# ValetudoV2.net
KiCad netlist of a schematic drawn in EAGLE
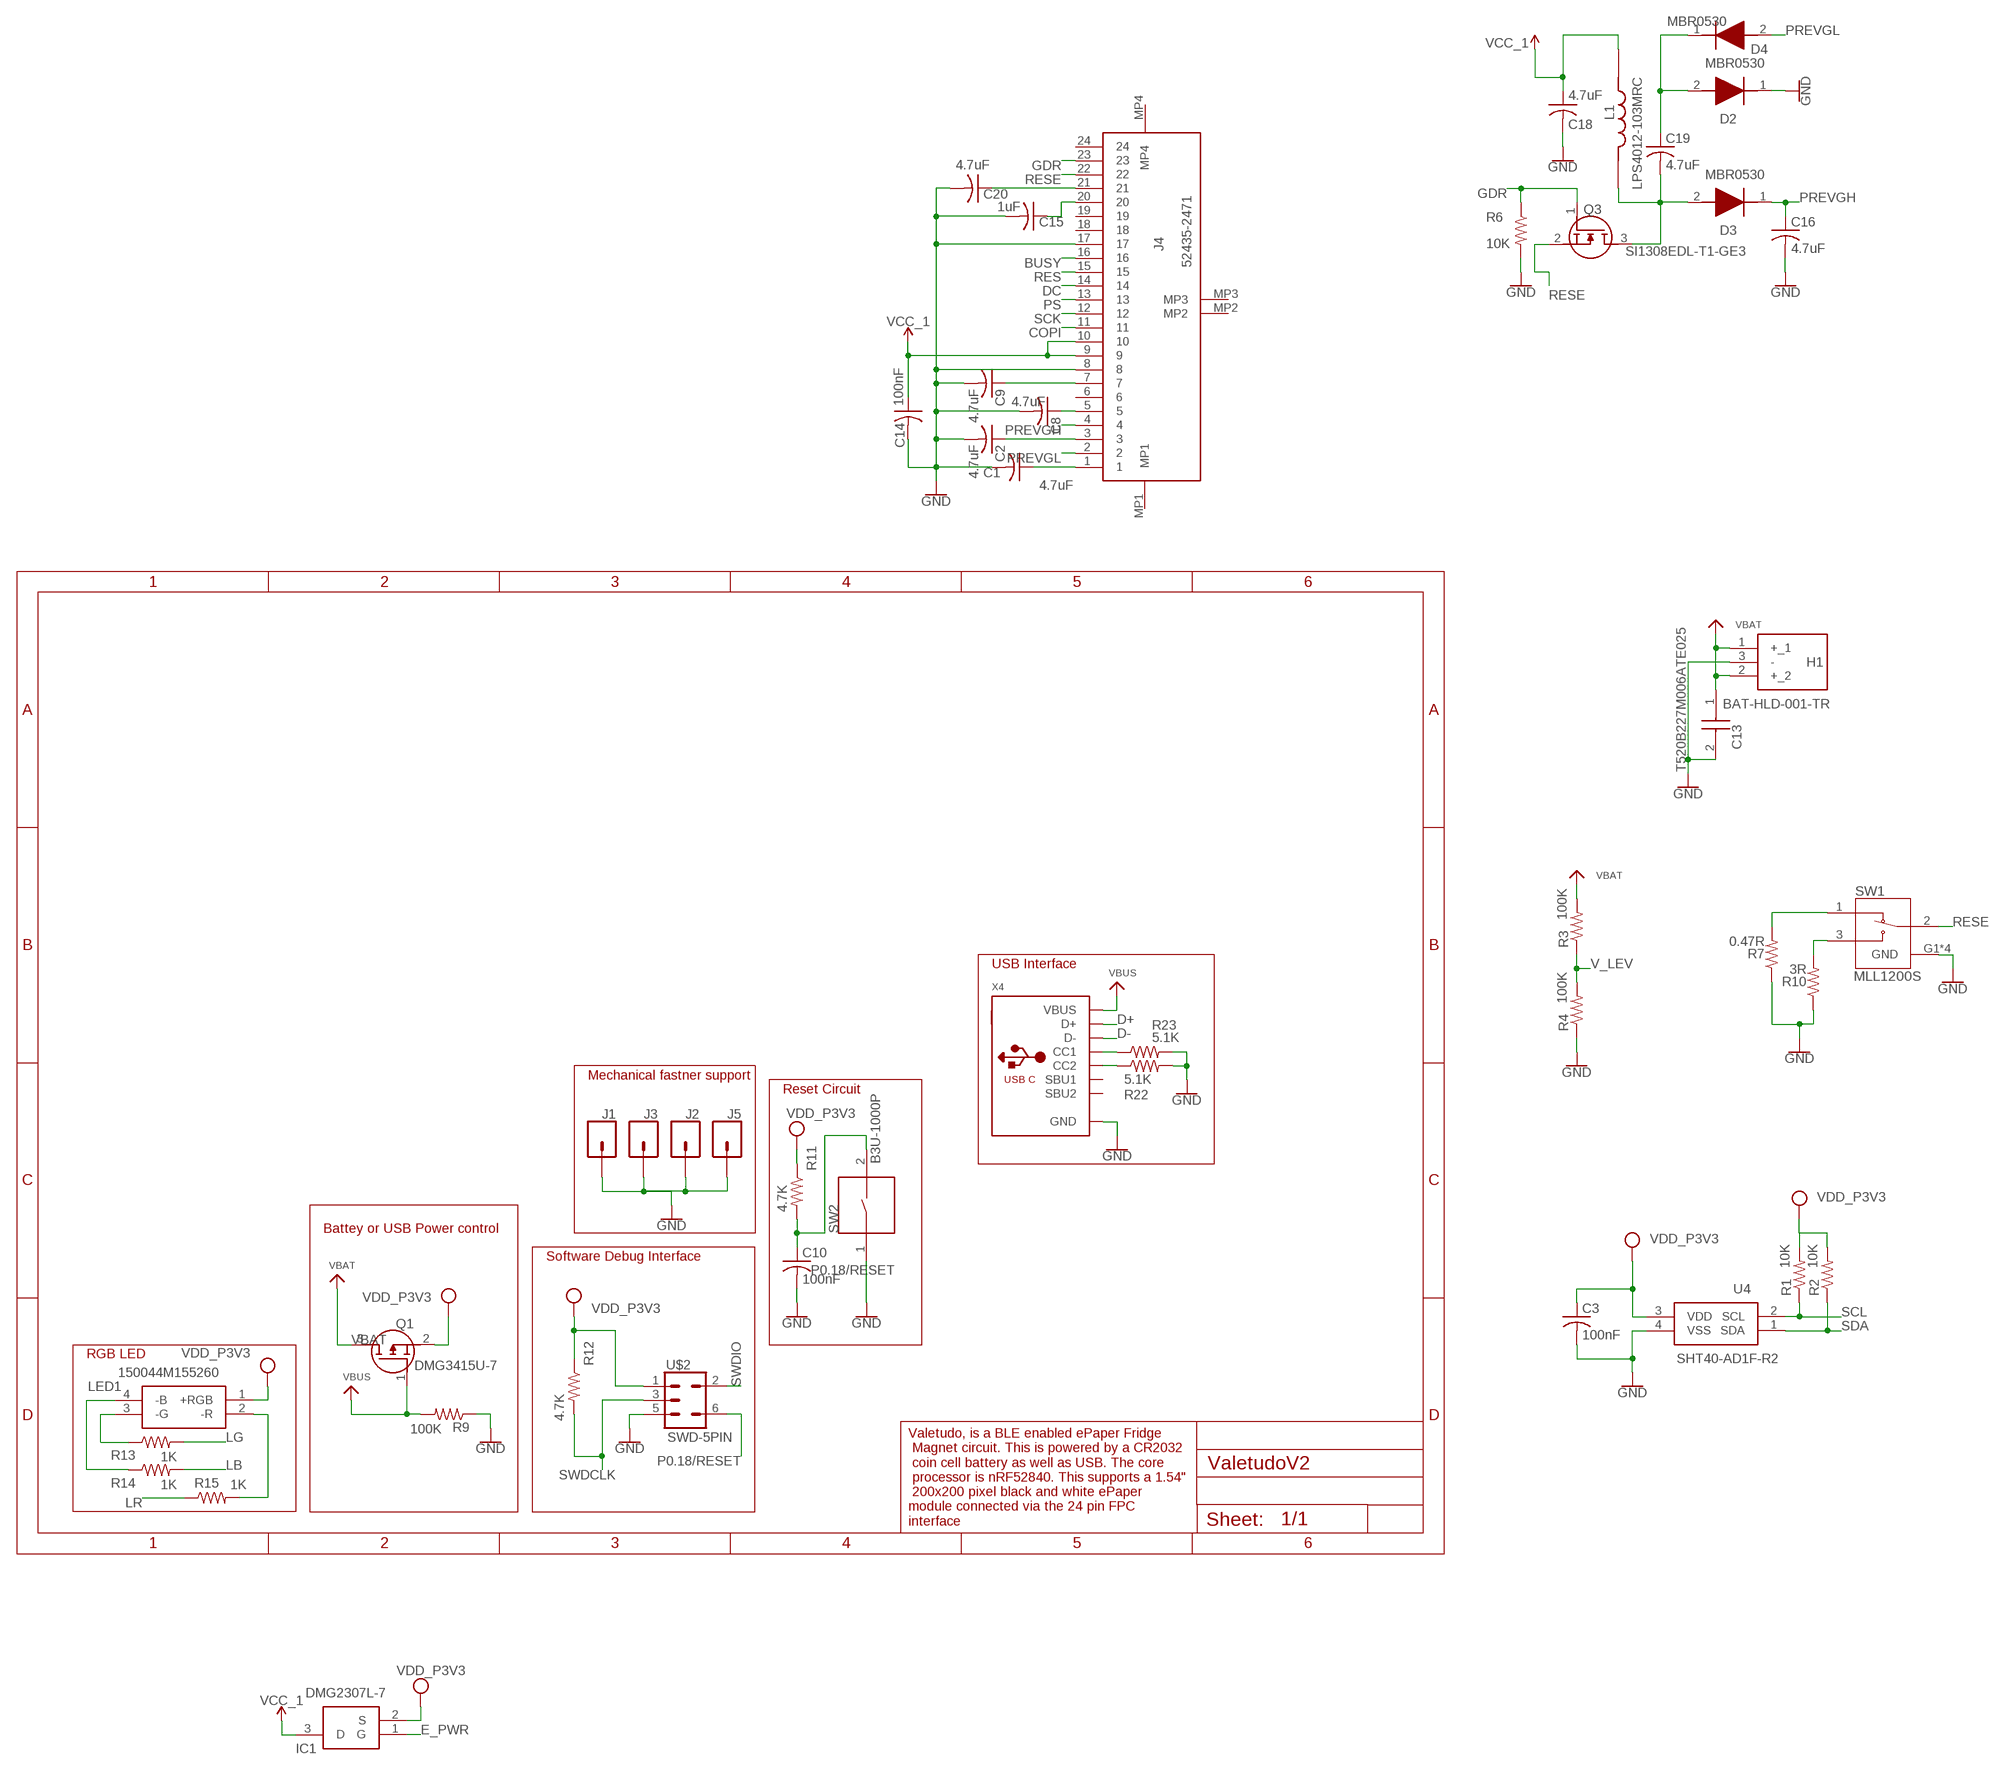
[diagram p0: schematic, sheet 1, part 1 of 2]
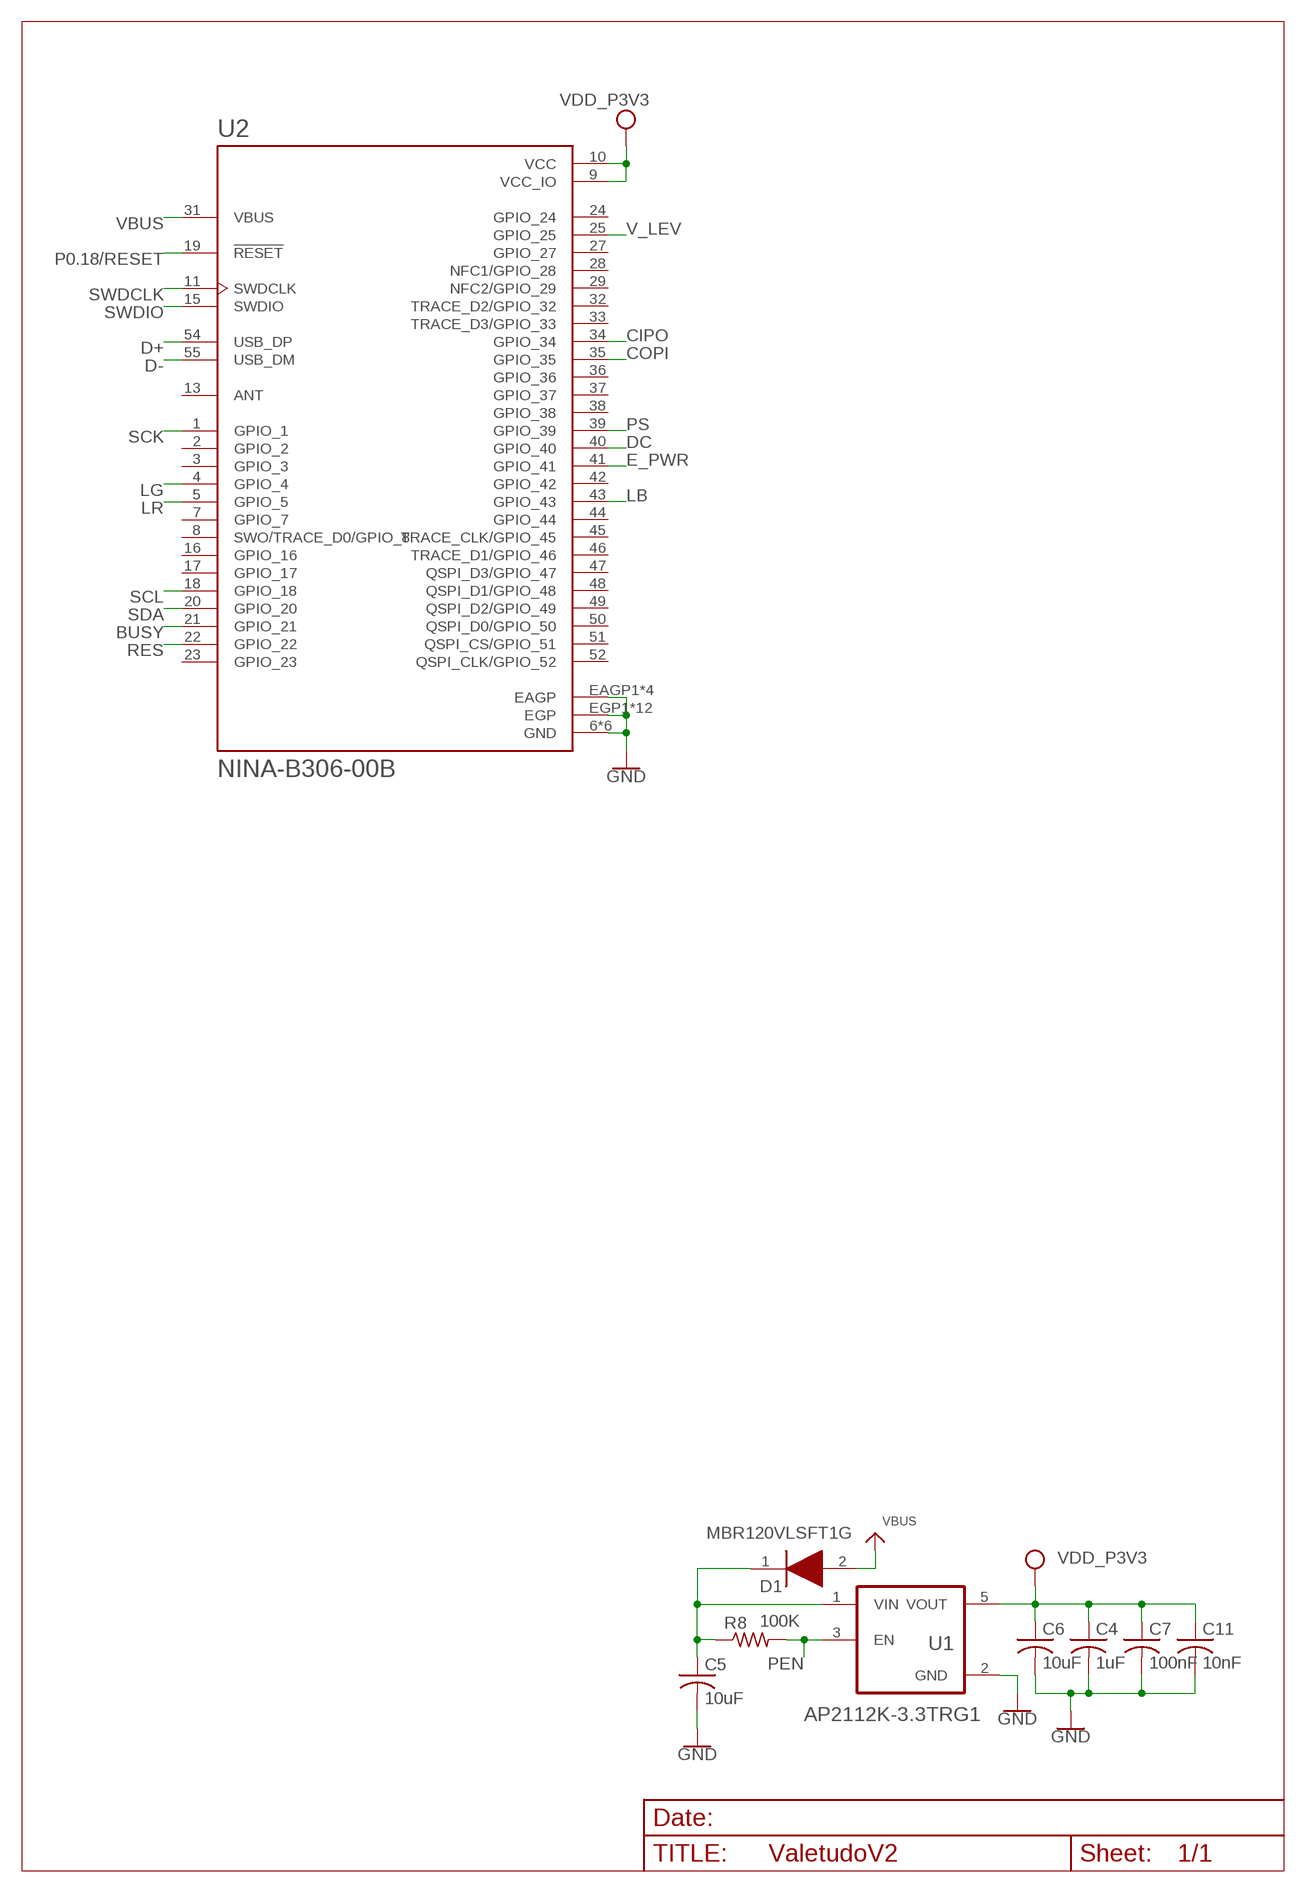
[diagram p1: schematic, sheet 1, part 2 of 2]

(export (version "E")
  (design (tool "Eeschema 10.0.6"))
  (components
    (comp (ref "C1")
      (value "4.7uF")
      (footprint "eagle-import:C0402")
      (libsource (lib "eagle-import") (part "C-USC0402"))
    )
    (comp (ref "C2")
      (value "4.7uF")
      (footprint "eagle-import:C0402")
      (libsource (lib "eagle-import") (part "C-USC0402"))
    )
    (comp (ref "C3")
      (value "100nF")
      (footprint "eagle-import:C0402")
      (libsource (lib "eagle-import") (part "C-USC0402"))
    )
    (comp (ref "C4")
      (value "1uF")
      (footprint "eagle-import:C0402")
      (libsource (lib "eagle-import") (part "C-USC0402"))
    )
    (comp (ref "C5")
      (value "10uF")
      (footprint "eagle-import:C0402")
      (libsource (lib "eagle-import") (part "C-USC0402"))
    )
    (comp (ref "C6")
      (value "10uF")
      (footprint "eagle-import:C0402")
      (libsource (lib "eagle-import") (part "C-USC0402"))
    )
    (comp (ref "C7")
      (value "100nF")
      (footprint "eagle-import:C0402")
      (libsource (lib "eagle-import") (part "C-USC0402"))
    )
    (comp (ref "C8")
      (value "4.7uF")
      (footprint "eagle-import:C0402")
      (libsource (lib "eagle-import") (part "C-USC0402"))
    )
    (comp (ref "C9")
      (value "4.7uF")
      (footprint "eagle-import:C0402")
      (libsource (lib "eagle-import") (part "C-USC0402"))
    )
    (comp (ref "C10")
      (value "100nF")
      (footprint "eagle-import:C0402")
      (libsource (lib "eagle-import") (part "C-USC0402"))
    )
    (comp (ref "C11")
      (value "10nF")
      (footprint "eagle-import:C0402")
      (libsource (lib "eagle-import") (part "C-USC0402"))
    )
    (comp (ref "C13")
      (value "T520B227M006ATE025")
      (footprint "eagle-import:T520B")
      (fields (field (name "MOUSER_PART_NUMBER") "80-T520B227M006ATE25"))
      (libsource (lib "eagle-import") (part "T520B227M006ATE025"))
    )
    (comp (ref "C14")
      (value "100nF")
      (footprint "eagle-import:C0402")
      (libsource (lib "eagle-import") (part "C-USC0402"))
    )
    (comp (ref "C15")
      (value "1uF")
      (footprint "eagle-import:C0402")
      (libsource (lib "eagle-import") (part "C-USC0402"))
    )
    (comp (ref "C16")
      (value "4.7uF")
      (footprint "eagle-import:C0402")
      (libsource (lib "eagle-import") (part "C-USC0402"))
    )
    (comp (ref "C18")
      (value "4.7uF")
      (footprint "eagle-import:C0402")
      (libsource (lib "eagle-import") (part "C-USC0402"))
    )
    (comp (ref "C19")
      (value "4.7uF")
      (footprint "eagle-import:C0402")
      (libsource (lib "eagle-import") (part "C-USC0402"))
    )
    (comp (ref "C20")
      (value "4.7uF")
      (footprint "eagle-import:C0402")
      (libsource (lib "eagle-import") (part "C-USC0402"))
    )
    (comp (ref "D1")
      (value "MBR120VLSFT1G")
      (footprint "eagle-import:SODFL3616X98N")
      (fields (field (name "MOUSER_PART_NUMBER") "863-MBR120VLSFT1G"))
      (libsource (lib "eagle-import") (part "MBR120VLSFT1G"))
    )
    (comp (ref "D2")
      (value "MBR0530")
      (footprint "eagle-import:SOD3716X135N")
      (fields (field (name "MOUSER_PART_NUMBER") "512-MBR0530"))
      (libsource (lib "eagle-import") (part "MBR0530"))
    )
    (comp (ref "D3")
      (value "MBR0530")
      (footprint "eagle-import:SOD3716X135N")
      (fields (field (name "MOUSER_PART_NUMBER") "512-MBR0530"))
      (libsource (lib "eagle-import") (part "MBR0530"))
    )
    (comp (ref "D4")
      (value "MBR0530")
      (footprint "eagle-import:SOD3716X135N")
      (fields (field (name "MOUSER_PART_NUMBER") "512-MBR0530"))
      (libsource (lib "eagle-import") (part "MBR0530"))
    )
    (comp (ref "H1")
      (value "BAT-HLD-001-TR")
      (footprint "eagle-import:BATHLD001TR")
      (fields (field (name "MOUSER_PART_NUMBER") "712-BAT-HLD-001-TR"))
      (libsource (lib "eagle-import") (part "BAT-HLD-001-TR"))
    )
    (comp (ref "IC1")
      (value "DMG2307L-7")
      (footprint "eagle-import:SOT96P240X110-3N")
      (libsource (lib "eagle-import") (part "DMG2307L-7"))
    )
    (comp (ref "J1")
      (value "CONN_01PTH_2MM")
      (footprint "eagle-import:1X01_2MM")
      (libsource (lib "eagle-import") (part "CONN_01PTH_2MM"))
    )
    (comp (ref "J2")
      (value "CONN_01PTH_2MM")
      (footprint "eagle-import:1X01_2MM")
      (libsource (lib "eagle-import") (part "CONN_01PTH_2MM"))
    )
    (comp (ref "J3")
      (value "CONN_01PTH_2MM")
      (footprint "eagle-import:1X01_2MM")
      (libsource (lib "eagle-import") (part "CONN_01PTH_2MM"))
    )
    (comp (ref "J4")
      (value "52435-2471")
      (footprint "eagle-import:524352471")
      (fields (field (name "MOUSER_PART_NUMBER") "538-52435-2471"))
      (libsource (lib "eagle-import") (part "52435-2471"))
    )
    (comp (ref "J5")
      (value "CONN_01PTH_2MM")
      (footprint "eagle-import:1X01_2MM")
      (libsource (lib "eagle-import") (part "CONN_01PTH_2MM"))
    )
    (comp (ref "L1")
      (value "LPS4012-103MRC")
      (footprint "eagle-import:IND_LPS4012-103MRC")
      (fields (field (name "MF") "Coilcraft"))
      (libsource (lib "eagle-import") (part "LPS4012-103MRC"))
    )
    (comp (ref "LED1")
      (value "150044M155260")
      (footprint "eagle-import:150044M155260")
      (fields (field (name "MOUSER_PART_NUMBER") "710-150044M155260"))
      (libsource (lib "eagle-import") (part "150044M155260"))
    )
    (comp (ref "Q1")
      (value "DMG3415U-7")
      (footprint "eagle-import:SOT96P240X100-3N")
      (fields (field (name "LCSC_PART_NUMBER") "C96616"))
      (libsource (lib "eagle-import") (part "DMG3415U-7"))
    )
    (comp (ref "Q3")
      (value "SI1308EDL-T1-GE3")
      (footprint "eagle-import:SOT65P210X110-3N")
      (fields
        (field (name "MANUFACTURER_PART_NUMBER") "Si1308EDL-T1-GE3")
        (field (name "MOUSER_PART_NUMBER") "78-SI1308EDL-T1-GE3")
      )
      (libsource (lib "eagle-import") (part "SI1308EDL-T1-GE3"))
    )
    (comp (ref "R1")
      (value "10K")
      (footprint "eagle-import:R0402")
      (libsource (lib "eagle-import") (part "R-US_R0402"))
    )
    (comp (ref "R2")
      (value "10K")
      (footprint "eagle-import:R0402")
      (libsource (lib "eagle-import") (part "R-US_R0402"))
    )
    (comp (ref "R3")
      (value "100K")
      (footprint "eagle-import:R0402")
      (libsource (lib "eagle-import") (part "R-US_R0402"))
    )
    (comp (ref "R4")
      (value "100K")
      (footprint "eagle-import:R0402")
      (libsource (lib "eagle-import") (part "R-US_R0402"))
    )
    (comp (ref "R6")
      (value "10K")
      (footprint "eagle-import:R0402")
      (libsource (lib "eagle-import") (part "R-US_R0402"))
    )
    (comp (ref "R7")
      (value "0.47R")
      (footprint "eagle-import:R0402")
      (libsource (lib "eagle-import") (part "R-US_R0402"))
    )
    (comp (ref "R8")
      (value "100K")
      (footprint "eagle-import:R0402")
      (libsource (lib "eagle-import") (part "R-US_R0402"))
    )
    (comp (ref "R9")
      (value "100K")
      (footprint "eagle-import:R0402")
      (libsource (lib "eagle-import") (part "R-US_R0402"))
    )
    (comp (ref "R10")
      (value "3R")
      (footprint "eagle-import:R0402")
      (libsource (lib "eagle-import") (part "R-US_R0402"))
    )
    (comp (ref "R11")
      (value "4.7K")
      (footprint "eagle-import:R0402")
      (libsource (lib "eagle-import") (part "R-US_R0402"))
    )
    (comp (ref "R12")
      (value "4.7K")
      (footprint "eagle-import:R0402")
      (libsource (lib "eagle-import") (part "R-US_R0402"))
    )
    (comp (ref "R13")
      (value "1K")
      (footprint "eagle-import:R0402")
      (libsource (lib "eagle-import") (part "R-US_R0402"))
    )
    (comp (ref "R14")
      (value "1K")
      (footprint "eagle-import:R0402")
      (libsource (lib "eagle-import") (part "R-US_R0402"))
    )
    (comp (ref "R15")
      (value "1K")
      (footprint "eagle-import:R0402")
      (libsource (lib "eagle-import") (part "R-US_R0402"))
    )
    (comp (ref "R22")
      (value "5.1K")
      (footprint "eagle-import:R0402")
      (libsource (lib "eagle-import") (part "R-US_R0402"))
    )
    (comp (ref "R23")
      (value "5.1K")
      (footprint "eagle-import:R0402")
      (libsource (lib "eagle-import") (part "R-US_R0402"))
    )
    (comp (ref "SW1")
      (value "MLL1200S")
      (footprint "eagle-import:SW_MLL1200S")
      (fields (field (name "COMMENT") "1437575-1") (field (name "MF") "TE Connectivity"))
      (libsource (lib "eagle-import") (part "MLL1200S"))
    )
    (comp (ref "SW2")
      (value "B3U-1000P")
      (footprint "eagle-import:SW_B3U-1000P")
      (fields (field (name "MF") "Omron"))
      (libsource (lib "eagle-import") (part "B3U-1000P"))
    )
    (comp (ref "U$2")
      (value "SWD-5PIN")
      (footprint "eagle-import:PAD_05_03X2_TP_NO4")
      (libsource (lib "eagle-import") (part "SWD-5PIN"))
    )
    (comp (ref "U1")
      (value "AP2112K-3.3TRG1")
      (footprint "eagle-import:SOT95P285X140-5N")
      (fields (field (name "MF") "Diodes Inc."))
      (libsource (lib "eagle-import") (part "AP2112K-3.3TRG1"))
    )
    (comp (ref "U2")
      (value "NINA-B306-00B")
      (footprint "eagle-import:XCVR_NINA-B306-00B")
      (fields (field (name "MF") "U-Blox"))
      (libsource (lib "eagle-import") (part "NINA-B306-00B"))
    )
    (comp (ref "U4")
      (value "SHT40-AD1F-R2")
      (footprint "eagle-import:SHT40AD1FR2")
      (fields (field (name "MOUSER_PART_NUMBER") "403-SHT40-AD1F-R2"))
      (libsource (lib "eagle-import") (part "SHT40-AD1F-R2"))
    )
    (comp (ref "X4")
      (value "MICROBUILDER_USB_C")
      (footprint "eagle-import:MICROBUILDER_USB_C_CUSB31-CFM2AX-01-X")
      (libsource (lib "eagle-import") (part "MICROBUILDER_USB_C"))
    )
  )
  (nets
    (net (code "1") (name "/BUSY") (class "Default")
      (node (ref "J4") (pin "16") (pinfunction "16_16") (pintype "bidirectional"))
      (node (ref "U2") (pin "21") (pinfunction "GPIO_21_21") (pintype "bidirectional"))
    )
    (net (code "2") (name "/CIPO") (class "Default")
      (node (ref "U2") (pin "34") (pinfunction "GPIO_34_34") (pintype "bidirectional"))
    )
    (net (code "3") (name "/COPI") (class "Default")
      (node (ref "J4") (pin "11") (pinfunction "11_11") (pintype "bidirectional"))
      (node (ref "U2") (pin "35") (pinfunction "GPIO_35_35") (pintype "bidirectional"))
    )
    (net (code "4") (name "/D+") (class "Default")
      (node (ref "U2") (pin "54") (pinfunction "USB_DP_54") (pintype "bidirectional"))
      (node (ref "X4") (pin "A6") (pinfunction "D+_A6") (pintype "bidirectional"))
      (node (ref "X4") (pin "B6") (pinfunction "D+_B6") (pintype "bidirectional"))
    )
    (net (code "5") (name "/D-") (class "Default")
      (node (ref "U2") (pin "55") (pinfunction "USB_DM_55") (pintype "bidirectional"))
      (node (ref "X4") (pin "A7") (pinfunction "D-_A7") (pintype "bidirectional"))
      (node (ref "X4") (pin "B7") (pinfunction "D-_B7") (pintype "bidirectional"))
    )
    (net (code "6") (name "/DC") (class "Default")
      (node (ref "J4") (pin "14") (pinfunction "14_14") (pintype "bidirectional"))
      (node (ref "U2") (pin "40") (pinfunction "GPIO_40_40") (pintype "bidirectional"))
    )
    (net (code "7") (name "/E_PWR") (class "Default")
      (node (ref "IC1") (pin "1") (pinfunction "G_1") (pintype "bidirectional"))
      (node (ref "U2") (pin "41") (pinfunction "GPIO_41_41") (pintype "bidirectional"))
    )
    (net (code "8") (name "/GDR") (class "Default")
      (node (ref "J4") (pin "23") (pinfunction "23_23") (pintype "bidirectional"))
      (node (ref "Q3") (pin "1") (pinfunction "G_1") (pintype "bidirectional"))
      (node (ref "R6") (pin "1") (pinfunction "1_1") (pintype "passive"))
    )
    (net (code "9") (name "/LB") (class "Default")
      (node (ref "R14") (pin "2") (pinfunction "2_2") (pintype "passive"))
      (node (ref "U2") (pin "43") (pinfunction "GPIO_43_43") (pintype "bidirectional"))
    )
    (net (code "10") (name "/LG") (class "Default")
      (node (ref "R13") (pin "2") (pinfunction "2_2") (pintype "passive"))
      (node (ref "U2") (pin "4") (pinfunction "GPIO_4_4") (pintype "bidirectional"))
    )
    (net (code "11") (name "/LR") (class "Default")
      (node (ref "R15") (pin "1") (pinfunction "1_1") (pintype "passive"))
      (node (ref "U2") (pin "5") (pinfunction "GPIO_5_5") (pintype "bidirectional"))
    )
    (net (code "12") (name "/P0.18{slash}RESET") (class "Default")
      (node (ref "C10") (pin "1") (pinfunction "1_1") (pintype "passive"))
      (node (ref "R11") (pin "2") (pinfunction "2_2") (pintype "passive"))
      (node (ref "SW2") (pin "2") (pinfunction "2_2") (pintype "passive"))
      (node (ref "U$2") (pin "6") (pinfunction "6_6") (pintype "bidirectional"))
      (node (ref "U2") (pin "19") (pinfunction "~{RESET}_19") (pintype "bidirectional"))
    )
    (net (code "13") (name "/PEN") (class "Default")
      (node (ref "R8") (pin "2") (pinfunction "2_2") (pintype "passive"))
      (node (ref "U1") (pin "3") (pinfunction "EN_3") (pintype "input"))
    )
    (net (code "14") (name "/PREVGH") (class "Default")
      (node (ref "C16") (pin "1") (pinfunction "1_1") (pintype "passive"))
      (node (ref "D3") (pin "1") (pinfunction "K_1") (pintype "bidirectional"))
      (node (ref "J4") (pin "4") (pinfunction "4_4") (pintype "bidirectional"))
    )
    (net (code "15") (name "/PREVGL") (class "Default")
      (node (ref "D4") (pin "2") (pinfunction "A_2") (pintype "bidirectional"))
      (node (ref "J4") (pin "2") (pinfunction "2_2") (pintype "bidirectional"))
    )
    (net (code "16") (name "/PS") (class "Default")
      (node (ref "J4") (pin "13") (pinfunction "13_13") (pintype "bidirectional"))
      (node (ref "U2") (pin "39") (pinfunction "GPIO_39_39") (pintype "bidirectional"))
    )
    (net (code "17") (name "/RES") (class "Default")
      (node (ref "J4") (pin "15") (pinfunction "15_15") (pintype "bidirectional"))
      (node (ref "U2") (pin "22") (pinfunction "GPIO_22_22") (pintype "bidirectional"))
    )
    (net (code "18") (name "/RESE") (class "Default")
      (node (ref "J4") (pin "22") (pinfunction "22_22") (pintype "bidirectional"))
      (node (ref "Q3") (pin "2") (pinfunction "S_2") (pintype "bidirectional"))
      (node (ref "SW1") (pin "2") (pinfunction "2_2") (pintype "passive"))
    )
    (net (code "19") (name "/SCK") (class "Default")
      (node (ref "J4") (pin "12") (pinfunction "12_12") (pintype "bidirectional"))
      (node (ref "U2") (pin "1") (pinfunction "GPIO_1_1") (pintype "bidirectional"))
    )
    (net (code "20") (name "/SCL") (class "Default")
      (node (ref "R1") (pin "1") (pinfunction "1_1") (pintype "passive"))
      (node (ref "U2") (pin "18") (pinfunction "GPIO_18_18") (pintype "bidirectional"))
      (node (ref "U4") (pin "2") (pinfunction "SCL_2") (pintype "bidirectional"))
    )
    (net (code "21") (name "/SDA") (class "Default")
      (node (ref "R2") (pin "1") (pinfunction "1_1") (pintype "passive"))
      (node (ref "U2") (pin "20") (pinfunction "GPIO_20_20") (pintype "bidirectional"))
      (node (ref "U4") (pin "1") (pinfunction "SDA_1") (pintype "bidirectional"))
    )
    (net (code "22") (name "/SWDCLK") (class "Default")
      (node (ref "R12") (pin "2") (pinfunction "2_2") (pintype "passive"))
      (node (ref "U$2") (pin "3") (pinfunction "3_3") (pintype "bidirectional"))
      (node (ref "U2") (pin "11") (pinfunction "SWDCLK_11") (pintype "input"))
    )
    (net (code "23") (name "/SWDIO") (class "Default")
      (node (ref "U$2") (pin "2") (pinfunction "2_2") (pintype "bidirectional"))
      (node (ref "U2") (pin "15") (pinfunction "SWDIO_15") (pintype "bidirectional"))
    )
    (net (code "24") (name "/V_LEV") (class "Default")
      (node (ref "R3") (pin "1") (pinfunction "1_1") (pintype "passive"))
      (node (ref "R4") (pin "2") (pinfunction "2_2") (pintype "passive"))
      (node (ref "U2") (pin "25") (pinfunction "GPIO_25_25") (pintype "bidirectional"))
    )
    (net (code "25") (name "GND") (class "Default")
      (node (ref "C1") (pin "2") (pinfunction "2_2") (pintype "passive"))
      (node (ref "C10") (pin "2") (pinfunction "2_2") (pintype "passive"))
      (node (ref "C11") (pin "2") (pinfunction "2_2") (pintype "passive"))
      (node (ref "C13") (pin "2") (pinfunction "-_2") (pintype "bidirectional"))
      (node (ref "C14") (pin "2") (pinfunction "2_2") (pintype "passive"))
      (node (ref "C15") (pin "2") (pinfunction "2_2") (pintype "passive"))
      (node (ref "C16") (pin "2") (pinfunction "2_2") (pintype "passive"))
      (node (ref "C18") (pin "2") (pinfunction "2_2") (pintype "passive"))
      (node (ref "C2") (pin "2") (pinfunction "2_2") (pintype "passive"))
      (node (ref "C20") (pin "2") (pinfunction "2_2") (pintype "passive"))
      (node (ref "C3") (pin "2") (pinfunction "2_2") (pintype "passive"))
      (node (ref "C4") (pin "2") (pinfunction "2_2") (pintype "passive"))
      (node (ref "C5") (pin "2") (pinfunction "2_2") (pintype "passive"))
      (node (ref "C6") (pin "2") (pinfunction "2_2") (pintype "passive"))
      (node (ref "C7") (pin "2") (pinfunction "2_2") (pintype "passive"))
      (node (ref "C8") (pin "2") (pinfunction "2_2") (pintype "passive"))
      (node (ref "C9") (pin "2") (pinfunction "2_2") (pintype "passive"))
      (node (ref "D2") (pin "1") (pinfunction "K_1") (pintype "bidirectional"))
      (node (ref "H1") (pin "3") (pinfunction "-_3") (pintype "bidirectional"))
      (node (ref "J1") (pin "1") (pinfunction "1_1") (pintype "passive"))
      (node (ref "J2") (pin "1") (pinfunction "1_1") (pintype "passive"))
      (node (ref "J3") (pin "1") (pinfunction "1_1") (pintype "passive"))
      (node (ref "J4") (pin "17") (pinfunction "17_17") (pintype "bidirectional"))
      (node (ref "J4") (pin "8") (pinfunction "8_8") (pintype "bidirectional"))
      (node (ref "J5") (pin "1") (pinfunction "1_1") (pintype "passive"))
      (node (ref "R10") (pin "1") (pinfunction "1_1") (pintype "passive"))
      (node (ref "R22") (pin "2") (pinfunction "2_2") (pintype "passive"))
      (node (ref "R23") (pin "2") (pinfunction "2_2") (pintype "passive"))
      (node (ref "R4") (pin "1") (pinfunction "1_1") (pintype "passive"))
      (node (ref "R6") (pin "2") (pinfunction "2_2") (pintype "passive"))
      (node (ref "R7") (pin "1") (pinfunction "1_1") (pintype "passive"))
      (node (ref "R9") (pin "1") (pinfunction "1_1") (pintype "passive"))
      (node (ref "SW1") (pin "G1") (pinfunction "GND_G1") (pintype "power_in"))
      (node (ref "SW1") (pin "G2") (pinfunction "GND_G2") (pintype "power_in"))
      (node (ref "SW1") (pin "G3") (pinfunction "GND_G3") (pintype "power_in"))
      (node (ref "SW1") (pin "G4") (pinfunction "GND_G4") (pintype "power_in"))
      (node (ref "SW2") (pin "1") (pinfunction "1_1") (pintype "passive"))
      (node (ref "U$2") (pin "5") (pinfunction "5_5") (pintype "bidirectional"))
      (node (ref "U1") (pin "2") (pinfunction "GND_2") (pintype "power_in"))
      (node (ref "U2") (pin "12") (pinfunction "GND_12") (pintype "power_in"))
      (node (ref "U2") (pin "14") (pinfunction "GND_14") (pintype "power_in"))
      (node (ref "U2") (pin "26") (pinfunction "GND_26") (pintype "power_in"))
      (node (ref "U2") (pin "30") (pinfunction "GND_30") (pintype "power_in"))
      (node (ref "U2") (pin "53") (pinfunction "GND_53") (pintype "power_in"))
      (node (ref "U2") (pin "6") (pinfunction "GND_6") (pintype "power_in"))
      (node (ref "U2") (pin "EAGP1") (pinfunction "EAGP_EAGP1") (pintype "power_in"))
      (node (ref "U2") (pin "EAGP2") (pinfunction "EAGP_EAGP2") (pintype "power_in"))
      (node (ref "U2") (pin "EAGP3") (pinfunction "EAGP_EAGP3") (pintype "power_in"))
      (node (ref "U2") (pin "EAGP4") (pinfunction "EAGP_EAGP4") (pintype "power_in"))
      (node (ref "U2") (pin "EGP1") (pinfunction "EGP_EGP1") (pintype "power_in"))
      (node (ref "U2") (pin "EGP10") (pinfunction "EGP_EGP10") (pintype "power_in"))
      (node (ref "U2") (pin "EGP11") (pinfunction "EGP_EGP11") (pintype "power_in"))
      (node (ref "U2") (pin "EGP12") (pinfunction "EGP_EGP12") (pintype "power_in"))
      (node (ref "U2") (pin "EGP2") (pinfunction "EGP_EGP2") (pintype "power_in"))
      (node (ref "U2") (pin "EGP3") (pinfunction "EGP_EGP3") (pintype "power_in"))
      (node (ref "U2") (pin "EGP4") (pinfunction "EGP_EGP4") (pintype "power_in"))
      (node (ref "U2") (pin "EGP5") (pinfunction "EGP_EGP5") (pintype "power_in"))
      (node (ref "U2") (pin "EGP6") (pinfunction "EGP_EGP6") (pintype "power_in"))
      (node (ref "U2") (pin "EGP7") (pinfunction "EGP_EGP7") (pintype "power_in"))
      (node (ref "U2") (pin "EGP8") (pinfunction "EGP_EGP8") (pintype "power_in"))
      (node (ref "U2") (pin "EGP9") (pinfunction "EGP_EGP9") (pintype "power_in"))
      (node (ref "U4") (pin "4") (pinfunction "VSS_4") (pintype "bidirectional"))
      (node (ref "X4") (pin "A1B12") (pinfunction "GND_A1B12") (pintype "power_in"))
      (node (ref "X4") (pin "B1A12") (pinfunction "GND_B1A12") (pintype "power_in"))
    )
    (net (code "26") (name "Net-(C1-Pad1)") (class "Default")
      (node (ref "C1") (pin "1") (pinfunction "1_1") (pintype "passive"))
      (node (ref "J4") (pin "1") (pinfunction "1_1") (pintype "bidirectional"))
    )
    (net (code "27") (name "Net-(C2-Pad1)") (class "Default")
      (node (ref "C2") (pin "1") (pinfunction "1_1") (pintype "passive"))
      (node (ref "J4") (pin "3") (pinfunction "3_3") (pintype "bidirectional"))
    )
    (net (code "28") (name "Net-(C8-Pad1)") (class "Default")
      (node (ref "C8") (pin "1") (pinfunction "1_1") (pintype "passive"))
      (node (ref "J4") (pin "5") (pinfunction "5_5") (pintype "bidirectional"))
    )
    (net (code "29") (name "Net-(C9-Pad1)") (class "Default")
      (node (ref "C9") (pin "1") (pinfunction "1_1") (pintype "passive"))
      (node (ref "J4") (pin "7") (pinfunction "7_7") (pintype "bidirectional"))
    )
    (net (code "30") (name "Net-(C15-Pad1)") (class "Default")
      (node (ref "C15") (pin "1") (pinfunction "1_1") (pintype "passive"))
      (node (ref "J4") (pin "20") (pinfunction "20_20") (pintype "bidirectional"))
    )
    (net (code "31") (name "Net-(C20-Pad1)") (class "Default")
      (node (ref "C20") (pin "1") (pinfunction "1_1") (pintype "passive"))
      (node (ref "J4") (pin "21") (pinfunction "21_21") (pintype "bidirectional"))
    )
    (net (code "32") (name "Net-(D1-K)") (class "Default")
      (node (ref "C5") (pin "1") (pinfunction "1_1") (pintype "passive"))
      (node (ref "D1") (pin "1") (pinfunction "K_1") (pintype "bidirectional"))
      (node (ref "R8") (pin "1") (pinfunction "1_1") (pintype "passive"))
      (node (ref "U1") (pin "1") (pinfunction "VIN_1") (pintype "power_in"))
    )
    (net (code "33") (name "Net-(D2-A)") (class "Default")
      (node (ref "C19") (pin "1") (pinfunction "1_1") (pintype "passive"))
      (node (ref "D2") (pin "2") (pinfunction "A_2") (pintype "bidirectional"))
      (node (ref "D4") (pin "1") (pinfunction "K_1") (pintype "bidirectional"))
    )
    (net (code "34") (name "Net-(D3-A)") (class "Default")
      (node (ref "C19") (pin "2") (pinfunction "2_2") (pintype "passive"))
      (node (ref "D3") (pin "2") (pinfunction "A_2") (pintype "bidirectional"))
      (node (ref "L1") (pin "2") (pinfunction "2_2") (pintype "passive"))
      (node (ref "Q3") (pin "3") (pinfunction "D_3") (pintype "bidirectional"))
    )
    (net (code "35") (name "Net-(LED1--B)") (class "Default")
      (node (ref "LED1") (pin "4") (pinfunction "-B_4") (pintype "bidirectional"))
      (node (ref "R14") (pin "1") (pinfunction "1_1") (pintype "passive"))
    )
    (net (code "36") (name "Net-(LED1--G)") (class "Default")
      (node (ref "LED1") (pin "3") (pinfunction "-G_3") (pintype "bidirectional"))
      (node (ref "R13") (pin "1") (pinfunction "1_1") (pintype "passive"))
    )
    (net (code "37") (name "Net-(LED1--R)") (class "Default")
      (node (ref "LED1") (pin "2") (pinfunction "-R_2") (pintype "bidirectional"))
      (node (ref "R15") (pin "2") (pinfunction "2_2") (pintype "passive"))
    )
    (net (code "38") (name "Net-(R7-Pad2)") (class "Default")
      (node (ref "R7") (pin "2") (pinfunction "2_2") (pintype "passive"))
      (node (ref "SW1") (pin "1") (pinfunction "1_1") (pintype "passive"))
    )
    (net (code "39") (name "Net-(R10-Pad2)") (class "Default")
      (node (ref "R10") (pin "2") (pinfunction "2_2") (pintype "passive"))
      (node (ref "SW1") (pin "3") (pinfunction "3_3") (pintype "passive"))
    )
    (net (code "40") (name "Net-(X4-CC1)") (class "Default")
      (node (ref "R23") (pin "1") (pinfunction "1_1") (pintype "passive"))
      (node (ref "X4") (pin "A5") (pinfunction "CC1_A5") (pintype "bidirectional"))
    )
    (net (code "41") (name "Net-(X4-CC2)") (class "Default")
      (node (ref "R22") (pin "1") (pinfunction "1_1") (pintype "passive"))
      (node (ref "X4") (pin "B5") (pinfunction "CC2_B5") (pintype "bidirectional"))
    )
    (net (code "42") (name "VBAT") (class "Default")
      (node (ref "C13") (pin "1") (pinfunction "+_1") (pintype "bidirectional"))
      (node (ref "H1") (pin "1") (pinfunction "+_1_1") (pintype "bidirectional"))
      (node (ref "H1") (pin "2") (pinfunction "+_2_2") (pintype "bidirectional"))
      (node (ref "Q1") (pin "3") (pinfunction "D_3") (pintype "bidirectional"))
      (node (ref "R3") (pin "2") (pinfunction "2_2") (pintype "passive"))
    )
    (net (code "43") (name "VBUS") (class "Default")
      (node (ref "D1") (pin "2") (pinfunction "A_2") (pintype "bidirectional"))
      (node (ref "Q1") (pin "1") (pinfunction "G_1") (pintype "bidirectional"))
      (node (ref "R9") (pin "2") (pinfunction "2_2") (pintype "passive"))
      (node (ref "U2") (pin "31") (pinfunction "VBUS_31") (pintype "input"))
      (node (ref "X4") (pin "A4B9") (pinfunction "VBUS_A4B9") (pintype "power_in"))
      (node (ref "X4") (pin "B4A9") (pinfunction "VBUS_B4A9") (pintype "power_in"))
    )
    (net (code "44") (name "VCC_1") (class "Default")
      (node (ref "C14") (pin "1") (pinfunction "1_1") (pintype "passive"))
      (node (ref "C18") (pin "1") (pinfunction "1_1") (pintype "passive"))
      (node (ref "IC1") (pin "3") (pinfunction "D_3") (pintype "bidirectional"))
      (node (ref "J4") (pin "10") (pinfunction "10_10") (pintype "bidirectional"))
      (node (ref "J4") (pin "9") (pinfunction "9_9") (pintype "bidirectional"))
      (node (ref "L1") (pin "1") (pinfunction "1_1") (pintype "passive"))
    )
    (net (code "45") (name "VDD_P3V3") (class "Default")
      (node (ref "C11") (pin "1") (pinfunction "1_1") (pintype "passive"))
      (node (ref "C3") (pin "1") (pinfunction "1_1") (pintype "passive"))
      (node (ref "C4") (pin "1") (pinfunction "1_1") (pintype "passive"))
      (node (ref "C6") (pin "1") (pinfunction "1_1") (pintype "passive"))
      (node (ref "C7") (pin "1") (pinfunction "1_1") (pintype "passive"))
      (node (ref "IC1") (pin "2") (pinfunction "S_2") (pintype "bidirectional"))
      (node (ref "LED1") (pin "1") (pinfunction "+RGB_1") (pintype "bidirectional"))
      (node (ref "Q1") (pin "2") (pinfunction "S_2") (pintype "bidirectional"))
      (node (ref "R1") (pin "2") (pinfunction "2_2") (pintype "passive"))
      (node (ref "R11") (pin "1") (pinfunction "1_1") (pintype "passive"))
      (node (ref "R12") (pin "1") (pinfunction "1_1") (pintype "passive"))
      (node (ref "R2") (pin "2") (pinfunction "2_2") (pintype "passive"))
      (node (ref "U$2") (pin "1") (pinfunction "1_1") (pintype "bidirectional"))
      (node (ref "U1") (pin "5") (pinfunction "VOUT_5") (pintype "power_in"))
      (node (ref "U2") (pin "10") (pinfunction "VCC_10") (pintype "power_in"))
      (node (ref "U2") (pin "9") (pinfunction "VCC_IO_9") (pintype "power_in"))
      (node (ref "U4") (pin "3") (pinfunction "VDD_3") (pintype "bidirectional"))
    )
    (net (code "46") (name "unconnected-(J4-Pad6)") (class "Default")
      (node (ref "J4") (pin "6") (pinfunction "6_6") (pintype "bidirectional"))
    )
    (net (code "47") (name "unconnected-(J4-Pad18)") (class "Default")
      (node (ref "J4") (pin "18") (pinfunction "18_18") (pintype "bidirectional"))
    )
    (net (code "48") (name "unconnected-(J4-Pad19)") (class "Default")
      (node (ref "J4") (pin "19") (pinfunction "19_19") (pintype "bidirectional"))
    )
    (net (code "49") (name "unconnected-(J4-Pad24)") (class "Default")
      (node (ref "J4") (pin "24") (pinfunction "24_24") (pintype "bidirectional"))
    )
    (net (code "50") (name "unconnected-(J4-PadMP1)") (class "Default")
      (node (ref "J4") (pin "MP1") (pinfunction "MP1_MP1") (pintype "bidirectional"))
    )
    (net (code "51") (name "unconnected-(J4-PadMP2)") (class "Default")
      (node (ref "J4") (pin "MP2") (pinfunction "MP2_MP2") (pintype "bidirectional"))
    )
    (net (code "52") (name "unconnected-(J4-PadMP3)") (class "Default")
      (node (ref "J4") (pin "MP3") (pinfunction "MP3_MP3") (pintype "bidirectional"))
    )
    (net (code "53") (name "unconnected-(J4-PadMP4)") (class "Default")
      (node (ref "J4") (pin "MP4") (pinfunction "MP4_MP4") (pintype "bidirectional"))
    )
    (net (code "54") (name "unconnected-(U2-ANT-Pad13)") (class "Default")
      (node (ref "U2") (pin "13") (pinfunction "ANT_13") (pintype "bidirectional"))
    )
    (net (code "55") (name "unconnected-(U2-GPIO_2-Pad2)") (class "Default")
      (node (ref "U2") (pin "2") (pinfunction "GPIO_2_2") (pintype "bidirectional"))
    )
    (net (code "56") (name "unconnected-(U2-GPIO_3-Pad3)") (class "Default")
      (node (ref "U2") (pin "3") (pinfunction "GPIO_3_3") (pintype "bidirectional"))
    )
    (net (code "57") (name "unconnected-(U2-GPIO_7-Pad7)") (class "Default")
      (node (ref "U2") (pin "7") (pinfunction "GPIO_7_7") (pintype "bidirectional"))
    )
    (net (code "58") (name "unconnected-(U2-GPIO_16-Pad16)") (class "Default")
      (node (ref "U2") (pin "16") (pinfunction "GPIO_16_16") (pintype "bidirectional"))
    )
    (net (code "59") (name "unconnected-(U2-GPIO_17-Pad17)") (class "Default")
      (node (ref "U2") (pin "17") (pinfunction "GPIO_17_17") (pintype "bidirectional"))
    )
    (net (code "60") (name "unconnected-(U2-GPIO_23-Pad23)") (class "Default")
      (node (ref "U2") (pin "23") (pinfunction "GPIO_23_23") (pintype "bidirectional"))
    )
    (net (code "61") (name "unconnected-(U2-GPIO_24-Pad24)") (class "Default")
      (node (ref "U2") (pin "24") (pinfunction "GPIO_24_24") (pintype "bidirectional"))
    )
    (net (code "62") (name "unconnected-(U2-GPIO_27-Pad27)") (class "Default")
      (node (ref "U2") (pin "27") (pinfunction "GPIO_27_27") (pintype "bidirectional"))
    )
    (net (code "63") (name "unconnected-(U2-GPIO_36-Pad36)") (class "Default")
      (node (ref "U2") (pin "36") (pinfunction "GPIO_36_36") (pintype "bidirectional"))
    )
    (net (code "64") (name "unconnected-(U2-GPIO_37-Pad37)") (class "Default")
      (node (ref "U2") (pin "37") (pinfunction "GPIO_37_37") (pintype "bidirectional"))
    )
    (net (code "65") (name "unconnected-(U2-GPIO_38-Pad38)") (class "Default")
      (node (ref "U2") (pin "38") (pinfunction "GPIO_38_38") (pintype "bidirectional"))
    )
    (net (code "66") (name "unconnected-(U2-GPIO_42-Pad42)") (class "Default")
      (node (ref "U2") (pin "42") (pinfunction "GPIO_42_42") (pintype "bidirectional"))
    )
    (net (code "67") (name "unconnected-(U2-GPIO_44-Pad44)") (class "Default")
      (node (ref "U2") (pin "44") (pinfunction "GPIO_44_44") (pintype "bidirectional"))
    )
    (net (code "68") (name "unconnected-(U2-NFC1{slash}GPIO_28-Pad28)") (class "Default")
      (node (ref "U2") (pin "28") (pinfunction "NFC1/GPIO_28_28") (pintype "bidirectional"))
    )
    (net (code "69") (name "unconnected-(U2-NFC2{slash}GPIO_29-Pad29)") (class "Default")
      (node (ref "U2") (pin "29") (pinfunction "NFC2/GPIO_29_29") (pintype "bidirectional"))
    )
    (net (code "70") (name "unconnected-(U2-QSPI_CLK{slash}GPIO_52-Pad52)") (class "Default")
      (node (ref "U2") (pin "52") (pinfunction "QSPI_CLK/GPIO_52_52") (pintype "bidirectional"))
    )
    (net (code "71") (name "unconnected-(U2-QSPI_CS{slash}GPIO_51-Pad51)") (class "Default")
      (node (ref "U2") (pin "51") (pinfunction "QSPI_CS/GPIO_51_51") (pintype "bidirectional"))
    )
    (net (code "72") (name "unconnected-(U2-QSPI_D0{slash}GPIO_50-Pad50)") (class "Default")
      (node (ref "U2") (pin "50") (pinfunction "QSPI_D0/GPIO_50_50") (pintype "bidirectional"))
    )
    (net (code "73") (name "unconnected-(U2-QSPI_D1{slash}GPIO_48-Pad48)") (class "Default")
      (node (ref "U2") (pin "48") (pinfunction "QSPI_D1/GPIO_48_48") (pintype "bidirectional"))
    )
    (net (code "74") (name "unconnected-(U2-QSPI_D2{slash}GPIO_49-Pad49)") (class "Default")
      (node (ref "U2") (pin "49") (pinfunction "QSPI_D2/GPIO_49_49") (pintype "bidirectional"))
    )
    (net (code "75") (name "unconnected-(U2-QSPI_D3{slash}GPIO_47-Pad47)") (class "Default")
      (node (ref "U2") (pin "47") (pinfunction "QSPI_D3/GPIO_47_47") (pintype "bidirectional"))
    )
    (net (code "76") (name "unconnected-(U2-SWO{slash}TRACE_D0{slash}GPIO_8-Pad8)") (class "Default")
      (node (ref "U2") (pin "8") (pinfunction "SWO/TRACE_D0/GPIO_8_8") (pintype "bidirectional"))
    )
    (net (code "77") (name "unconnected-(U2-TRACE_CLK{slash}GPIO_45-Pad45)") (class "Default")
      (node (ref "U2") (pin "45") (pinfunction "TRACE_CLK/GPIO_45_45") (pintype "bidirectional"))
    )
    (net (code "78") (name "unconnected-(U2-TRACE_D1{slash}GPIO_46-Pad46)") (class "Default")
      (node (ref "U2") (pin "46") (pinfunction "TRACE_D1/GPIO_46_46") (pintype "bidirectional"))
    )
    (net (code "79") (name "unconnected-(U2-TRACE_D2{slash}GPIO_32-Pad32)") (class "Default")
      (node (ref "U2") (pin "32") (pinfunction "TRACE_D2/GPIO_32_32") (pintype "bidirectional"))
    )
    (net (code "80") (name "unconnected-(U2-TRACE_D3{slash}GPIO_33-Pad33)") (class "Default")
      (node (ref "U2") (pin "33") (pinfunction "TRACE_D3/GPIO_33_33") (pintype "bidirectional"))
    )
    (net (code "81") (name "unconnected-(X4-SBU1-PadA8)") (class "Default")
      (node (ref "X4") (pin "A8") (pinfunction "SBU1_A8") (pintype "bidirectional"))
    )
    (net (code "82") (name "unconnected-(X4-SBU2-PadB8)") (class "Default")
      (node (ref "X4") (pin "B8") (pinfunction "SBU2_B8") (pintype "bidirectional"))
    )
  )
)
